# Sport_Analyzer_Chronojump_Teensy_4.net
KiCad netlist of a schematic drawn in EAGLE
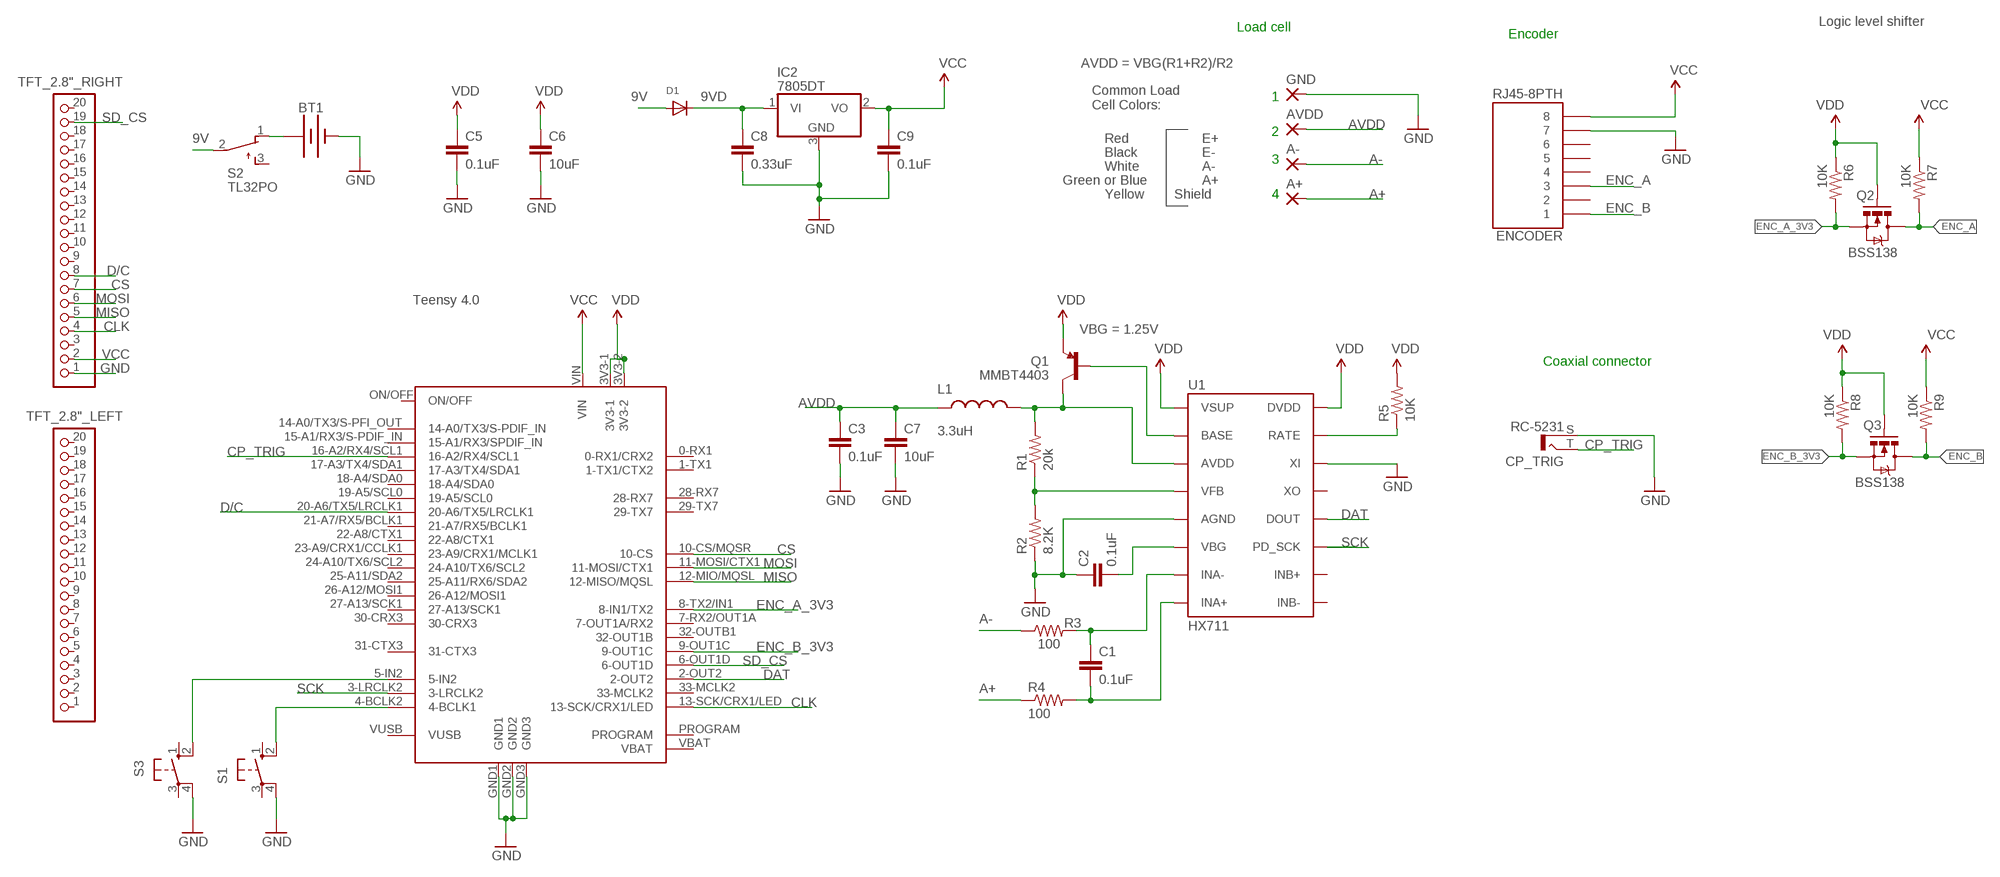
[diagram p0: schematic, sheet 1]

(export (version "E")
  (design (tool "Eeschema 10.0.6"))
  (components
    (comp (ref "A+")
      (value "3,81/1,4")
      (footprint "eagle-import:3,81_1,4")
      (libsource (lib "eagle-import") (part "3,81/1,4"))
    )
    (comp (ref "A-")
      (value "3,81/1,4")
      (footprint "eagle-import:3,81_1,4")
      (libsource (lib "eagle-import") (part "3,81/1,4"))
    )
    (comp (ref "AVDD")
      (value "3,81/1,4")
      (footprint "eagle-import:3,81_1,4")
      (libsource (lib "eagle-import") (part "3,81/1,4"))
    )
    (comp (ref "BT1")
      (value "BATTERY-9V")
      (footprint "eagle-import:BATTCON_9V")
      (libsource (lib "eagle-import") (part "BATTERY-9V"))
    )
    (comp (ref "C1")
      (value "0.1uF")
      (footprint "eagle-import:0603-CAP")
      (libsource (lib "eagle-import") (part "0.1UF-25V-5%(0603)"))
    )
    (comp (ref "C2")
      (value "0.1uF")
      (footprint "eagle-import:0603-CAP")
      (libsource (lib "eagle-import") (part "0.1UF-25V-5%(0603)"))
    )
    (comp (ref "C3")
      (value "0.1uF")
      (footprint "eagle-import:0603-CAP")
      (libsource (lib "eagle-import") (part "0.1UF-25V-5%(0603)"))
    )
    (comp (ref "C5")
      (value "0.1uF")
      (footprint "eagle-import:0603-CAP")
      (libsource (lib "eagle-import") (part "0.1UF-25V-5%(0603)"))
    )
    (comp (ref "C6")
      (value "10uF")
      (footprint "eagle-import:1210")
      (libsource (lib "eagle-import") (part "10UF50V20%(1210)"))
    )
    (comp (ref "C7")
      (value "10uF")
      (footprint "eagle-import:1210")
      (libsource (lib "eagle-import") (part "10UF50V20%(1210)"))
    )
    (comp (ref "C8")
      (value "0.33uF")
      (footprint "eagle-import:0603-CAP")
      (libsource (lib "eagle-import") (part "0.1UF-25V-5%(0603)"))
    )
    (comp (ref "C9")
      (value "0.1uF")
      (footprint "eagle-import:0603-CAP")
      (libsource (lib "eagle-import") (part "0.1UF-25V-5%(0603)"))
    )
    (comp (ref "CP_TRIG")
      (value "RC-5231")
      (footprint "eagle-import:RC-5231")
      (libsource (lib "eagle-import") (part "RC-5231"))
    )
    (comp (ref "D1")
      (value "DIODESOD-123")
      (footprint "eagle-import:SOD-123")
      (libsource (lib "eagle-import") (part "DIODESOD-123"))
    )
    (comp (ref "ENCODER")
      (value "RJ45-8PTH")
      (footprint "eagle-import:RJ45-8")
      (libsource (lib "eagle-import") (part "RJ45-8PTH"))
    )
    (comp (ref "GND")
      (value "3,81/1,4")
      (footprint "eagle-import:3,81_1,4")
      (libsource (lib "eagle-import") (part "3,81/1,4"))
    )
    (comp (ref "IC2")
      (value "7805DT")
      (footprint "eagle-import:TO252")
      (libsource (lib "eagle-import") (part "78DT05"))
    )
    (comp (ref "L1")
      (value "3.3uH")
      (footprint "eagle-import:0805")
      (libsource (lib "eagle-import") (part "INDUCTOR0805-IND"))
    )
    (comp (ref "Q1")
      (value "MMBT4403")
      (footprint "eagle-import:SOT23-3")
      (libsource (lib "eagle-import") (part "TRANSISTOR_PNPMMBT4403"))
    )
    (comp (ref "Q2")
      (value "BSS138")
      (footprint "eagle-import:SOT23-3")
      (libsource (lib "eagle-import") (part "MOSFET-NCHANNELSMD"))
    )
    (comp (ref "Q3")
      (value "BSS138")
      (footprint "eagle-import:SOT23-3")
      (libsource (lib "eagle-import") (part "MOSFET-NCHANNELSMD"))
    )
    (comp (ref "R1")
      (value "20k")
      (footprint "eagle-import:0603-RES")
      (libsource (lib "eagle-import") (part "20KOHM1/10W1%(0603)"))
    )
    (comp (ref "R2")
      (value "8.2K")
      (footprint "eagle-import:0603-RES")
      (libsource (lib "eagle-import") (part "8.2KOHM-1/10W-5%(0603)"))
    )
    (comp (ref "R3")
      (value "100")
      (footprint "eagle-import:0603-RES")
      (libsource (lib "eagle-import") (part "100OHM-1/10W-1%(0603)"))
    )
    (comp (ref "R4")
      (value "100")
      (footprint "eagle-import:0603-RES")
      (libsource (lib "eagle-import") (part "100OHM-1/10W-1%(0603)"))
    )
    (comp (ref "R5")
      (value "10K")
      (footprint "eagle-import:0603-RES")
      (libsource (lib "eagle-import") (part "10KOHM-1/10W-1%(0603)0603"))
    )
    (comp (ref "R6")
      (value "10K")
      (footprint "eagle-import:0603-RES")
      (libsource (lib "eagle-import") (part "RESISTOR0603-RES"))
    )
    (comp (ref "R7")
      (value "10K")
      (footprint "eagle-import:0603-RES")
      (libsource (lib "eagle-import") (part "RESISTOR0603-RES"))
    )
    (comp (ref "R8")
      (value "10K")
      (footprint "eagle-import:0603-RES")
      (libsource (lib "eagle-import") (part "RESISTOR0603-RES"))
    )
    (comp (ref "R9")
      (value "10K")
      (footprint "eagle-import:0603-RES")
      (libsource (lib "eagle-import") (part "RESISTOR0603-RES"))
    )
    (comp (ref "S1")
      (value "10-XX")
      (footprint "eagle-import:B3F-10XX")
      (fields (field (name "MPN") "B3F-1000"))
      (libsource (lib "eagle-import") (part "10-XX"))
    )
    (comp (ref "S2")
      (value "TL32PO")
      (footprint "eagle-import:TL3XPO")
      (libsource (lib "eagle-import") (part "TL32PO"))
    )
    (comp (ref "S3")
      (value "10-XX")
      (footprint "eagle-import:B3F-10XX")
      (fields (field (name "MPN") "B3F-1000"))
      (libsource (lib "eagle-import") (part "10-XX"))
    )
    (comp (ref "TFT_2.8\"_LEFT")
      (value "PINHD-1X20")
      (footprint "eagle-import:1X20")
      (libsource (lib "eagle-import") (part "PINHD-1X20"))
    )
    (comp (ref "TFT_2.8\"_RIGHT")
      (value "PINHD-1X20")
      (footprint "eagle-import:1X20")
      (libsource (lib "eagle-import") (part "PINHD-1X20"))
    )
    (comp (ref "U$2")
      (value "TEENSY40")
      (footprint "eagle-import:TEENSY40")
      (libsource (lib "eagle-import") (part "TEENSY40"))
    )
    (comp (ref "U1")
      (value "HX711")
      (footprint "eagle-import:SO16")
      (libsource (lib "eagle-import") (part "HX711HX711"))
    )
  )
  (nets
    (net (code "1") (name "/9V") (class "Default")
      (node (ref "D1") (pin "A") (pinfunction "A_A") (pintype "passive"))
      (node (ref "S2") (pin "2") (pinfunction "P_2") (pintype "passive"))
    )
    (net (code "2") (name "/9VD") (class "Default")
      (node (ref "C8") (pin "1") (pinfunction "1_1") (pintype "passive"))
      (node (ref "D1") (pin "C") (pinfunction "C_C") (pintype "passive"))
      (node (ref "IC2") (pin "1") (pinfunction "VI_1") (pintype "input"))
    )
    (net (code "3") (name "/A+") (class "Default")
      (node (ref "A+") (pin "1") (pinfunction "P_1") (pintype "passive"))
      (node (ref "R4") (pin "1") (pinfunction "1_1") (pintype "passive"))
    )
    (net (code "4") (name "/A-") (class "Default")
      (node (ref "A-") (pin "1") (pinfunction "P_1") (pintype "passive"))
      (node (ref "R3") (pin "1") (pinfunction "1_1") (pintype "passive"))
    )
    (net (code "5") (name "/AVDD") (class "Default")
      (node (ref "AVDD") (pin "1") (pinfunction "P_1") (pintype "passive"))
      (node (ref "C3") (pin "1") (pinfunction "1_1") (pintype "passive"))
      (node (ref "C7") (pin "1") (pinfunction "1_1") (pintype "passive"))
      (node (ref "L1") (pin "1") (pinfunction "1_1") (pintype "passive"))
    )
    (net (code "6") (name "/CLK") (class "Default")
      (node (ref "TFT_2.8\"_RIGHT") (pin "4") (pinfunction "4_4") (pintype "passive"))
      (node (ref "U$2") (pin "13-SCK/CRX1/LED") (pinfunction "13-SCK/CRX1/LED_13-SCK/CRX1/LED") (pintype "bidirectional"))
    )
    (net (code "7") (name "/CP_TRIG") (class "Default")
      (node (ref "CP_TRIG") (pin "T") (pinfunction "T_T") (pintype "passive"))
      (node (ref "U$2") (pin "16-A2/RX4/SCL1") (pinfunction "16-A2/RX4/SCL1_16-A2/RX4/SCL1") (pintype "bidirectional"))
    )
    (net (code "8") (name "/CS") (class "Default")
      (node (ref "TFT_2.8\"_RIGHT") (pin "7") (pinfunction "7_7") (pintype "passive"))
      (node (ref "U$2") (pin "10-CS/MQSR") (pinfunction "10-CS_10-CS/MQSR") (pintype "bidirectional"))
    )
    (net (code "9") (name "/DAT") (class "Default")
      (node (ref "U$2") (pin "2-OUT2") (pinfunction "2-OUT2_2-OUT2") (pintype "bidirectional"))
      (node (ref "U1") (pin "12") (pinfunction "DOUT_12") (pintype "bidirectional"))
    )
    (net (code "10") (name "/D{slash}C") (class "Default")
      (node (ref "TFT_2.8\"_RIGHT") (pin "8") (pinfunction "8_8") (pintype "passive"))
      (node (ref "U$2") (pin "20-A6/TX5/LRCLK1") (pinfunction "20-A6/TX5/LRCLK1_20-A6/TX5/LRCLK1") (pintype "bidirectional"))
    )
    (net (code "11") (name "/MISO") (class "Default")
      (node (ref "TFT_2.8\"_RIGHT") (pin "5") (pinfunction "5_5") (pintype "passive"))
      (node (ref "U$2") (pin "12-MIO/MQSL") (pinfunction "12-MISO/MQSL_12-MIO/MQSL") (pintype "bidirectional"))
    )
    (net (code "12") (name "/MOSI") (class "Default")
      (node (ref "TFT_2.8\"_RIGHT") (pin "6") (pinfunction "6_6") (pintype "passive"))
      (node (ref "U$2") (pin "11-MOSI/CTX1") (pinfunction "11-MOSI/CTX1_11-MOSI/CTX1") (pintype "bidirectional"))
    )
    (net (code "13") (name "/SCK") (class "Default")
      (node (ref "U$2") (pin "3-LRCLK2") (pinfunction "3-LRCLK2_3-LRCLK2") (pintype "bidirectional"))
      (node (ref "U1") (pin "11") (pinfunction "PD_SCK_11") (pintype "bidirectional"))
    )
    (net (code "14") (name "/SD_CS") (class "Default")
      (node (ref "TFT_2.8\"_RIGHT") (pin "19") (pinfunction "19_19") (pintype "passive"))
      (node (ref "U$2") (pin "6-OUT1D") (pinfunction "6-OUT1D_6-OUT1D") (pintype "bidirectional"))
    )
    (net (code "15") (name "ENC_A") (class "Default")
      (node (ref "ENCODER") (pin "3") (pinfunction "3_3") (pintype "bidirectional"))
      (node (ref "Q2") (pin "3") (pinfunction "D_3") (pintype "passive"))
      (node (ref "R7") (pin "2") (pinfunction "2_2") (pintype "passive"))
    )
    (net (code "16") (name "ENC_A_3V3") (class "Default")
      (node (ref "Q2") (pin "2") (pinfunction "S_2") (pintype "passive"))
      (node (ref "R6") (pin "2") (pinfunction "2_2") (pintype "passive"))
      (node (ref "U$2") (pin "8-TX2/IN1") (pinfunction "8-IN1/TX2_8-TX2/IN1") (pintype "bidirectional"))
    )
    (net (code "17") (name "ENC_B") (class "Default")
      (node (ref "ENCODER") (pin "1") (pinfunction "1_1") (pintype "bidirectional"))
      (node (ref "Q3") (pin "3") (pinfunction "D_3") (pintype "passive"))
      (node (ref "R9") (pin "2") (pinfunction "2_2") (pintype "passive"))
    )
    (net (code "18") (name "ENC_B_3V3") (class "Default")
      (node (ref "Q3") (pin "2") (pinfunction "S_2") (pintype "passive"))
      (node (ref "R8") (pin "2") (pinfunction "2_2") (pintype "passive"))
      (node (ref "U$2") (pin "9-OUT1C") (pinfunction "9-OUT1C_9-OUT1C") (pintype "bidirectional"))
    )
    (net (code "19") (name "GND") (class "Default")
      (node (ref "BT1") (pin "-") (pinfunction "-_-") (pintype "power_in"))
      (node (ref "C2") (pin "1") (pinfunction "1_1") (pintype "passive"))
      (node (ref "C3") (pin "2") (pinfunction "2_2") (pintype "passive"))
      (node (ref "C5") (pin "2") (pinfunction "2_2") (pintype "passive"))
      (node (ref "C6") (pin "2") (pinfunction "2_2") (pintype "passive"))
      (node (ref "C7") (pin "2") (pinfunction "2_2") (pintype "passive"))
      (node (ref "C8") (pin "2") (pinfunction "2_2") (pintype "passive"))
      (node (ref "C9") (pin "2") (pinfunction "2_2") (pintype "passive"))
      (node (ref "CP_TRIG") (pin "S") (pinfunction "S_S") (pintype "passive"))
      (node (ref "ENCODER") (pin "7") (pinfunction "7_7") (pintype "bidirectional"))
      (node (ref "GND") (pin "1") (pinfunction "P_1") (pintype "passive"))
      (node (ref "IC2") (pin "3") (pinfunction "GND_3") (pintype "passive"))
      (node (ref "R2") (pin "1") (pinfunction "1_1") (pintype "passive"))
      (node (ref "S1") (pin "4") (pinfunction "P1_4") (pintype "passive"))
      (node (ref "S3") (pin "4") (pinfunction "P1_4") (pintype "passive"))
      (node (ref "TFT_2.8\"_RIGHT") (pin "1") (pinfunction "1_1") (pintype "passive"))
      (node (ref "U$2") (pin "GND1") (pinfunction "GND1_GND1") (pintype "bidirectional"))
      (node (ref "U$2") (pin "GND2") (pinfunction "GND2_GND2") (pintype "bidirectional"))
      (node (ref "U$2") (pin "GND3") (pinfunction "GND3_GND3") (pintype "bidirectional"))
      (node (ref "U1") (pin "14") (pinfunction "XI_14") (pintype "bidirectional"))
      (node (ref "U1") (pin "5") (pinfunction "AGND_5") (pintype "bidirectional"))
    )
    (net (code "20") (name "Net-(Q1-B)") (class "Default")
      (node (ref "Q1") (pin "1") (pinfunction "B_1") (pintype "passive"))
      (node (ref "U1") (pin "2") (pinfunction "BASE_2") (pintype "bidirectional"))
    )
    (net (code "21") (name "Net-(Q1-C)") (class "Default")
      (node (ref "L1") (pin "2") (pinfunction "2_2") (pintype "passive"))
      (node (ref "Q1") (pin "3") (pinfunction "C_3") (pintype "passive"))
      (node (ref "R1") (pin "2") (pinfunction "2_2") (pintype "passive"))
      (node (ref "U1") (pin "3") (pinfunction "AVDD_3") (pintype "bidirectional"))
    )
    (net (code "22") (name "Net-(S1-S1)") (class "Default")
      (node (ref "S1") (pin "2") (pinfunction "S1_2") (pintype "passive"))
      (node (ref "U$2") (pin "4-BCLK2") (pinfunction "4-BCLK1_4-BCLK2") (pintype "bidirectional"))
    )
    (net (code "23") (name "Net-(S2-O)") (class "Default")
      (node (ref "BT1") (pin "+") (pinfunction "+_+") (pintype "power_in"))
      (node (ref "S2") (pin "1") (pinfunction "O_1") (pintype "passive"))
    )
    (net (code "24") (name "Net-(S3-S1)") (class "Default")
      (node (ref "S3") (pin "2") (pinfunction "S1_2") (pintype "passive"))
      (node (ref "U$2") (pin "5-IN2") (pinfunction "5-IN2_5-IN2") (pintype "bidirectional"))
    )
    (net (code "25") (name "Net-(U1-INA+)") (class "Default")
      (node (ref "C1") (pin "2") (pinfunction "2_2") (pintype "passive"))
      (node (ref "R4") (pin "2") (pinfunction "2_2") (pintype "passive"))
      (node (ref "U1") (pin "8") (pinfunction "INA+_8") (pintype "bidirectional"))
    )
    (net (code "26") (name "Net-(U1-INA-)") (class "Default")
      (node (ref "C1") (pin "1") (pinfunction "1_1") (pintype "passive"))
      (node (ref "R3") (pin "2") (pinfunction "2_2") (pintype "passive"))
      (node (ref "U1") (pin "7") (pinfunction "INA-_7") (pintype "bidirectional"))
    )
    (net (code "27") (name "Net-(U1-RATE)") (class "Default")
      (node (ref "R5") (pin "1") (pinfunction "1_1") (pintype "passive"))
      (node (ref "U1") (pin "15") (pinfunction "RATE_15") (pintype "bidirectional"))
    )
    (net (code "28") (name "Net-(U1-VBG)") (class "Default")
      (node (ref "C2") (pin "2") (pinfunction "2_2") (pintype "passive"))
      (node (ref "U1") (pin "6") (pinfunction "VBG_6") (pintype "bidirectional"))
    )
    (net (code "29") (name "Net-(U1-VFB)") (class "Default")
      (node (ref "R1") (pin "1") (pinfunction "1_1") (pintype "passive"))
      (node (ref "R2") (pin "2") (pinfunction "2_2") (pintype "passive"))
      (node (ref "U1") (pin "4") (pinfunction "VFB_4") (pintype "bidirectional"))
    )
    (net (code "30") (name "VCC") (class "Default")
      (node (ref "C9") (pin "1") (pinfunction "1_1") (pintype "passive"))
      (node (ref "ENCODER") (pin "8") (pinfunction "8_8") (pintype "bidirectional"))
      (node (ref "IC2") (pin "2") (pinfunction "VO_2") (pintype "passive"))
      (node (ref "R7") (pin "1") (pinfunction "1_1") (pintype "passive"))
      (node (ref "R9") (pin "1") (pinfunction "1_1") (pintype "passive"))
      (node (ref "TFT_2.8\"_RIGHT") (pin "2") (pinfunction "2_2") (pintype "passive"))
      (node (ref "U$2") (pin "VIN") (pinfunction "VIN_VIN") (pintype "bidirectional"))
    )
    (net (code "31") (name "VDD") (class "Default")
      (node (ref "C5") (pin "1") (pinfunction "1_1") (pintype "passive"))
      (node (ref "C6") (pin "1") (pinfunction "1_1") (pintype "passive"))
      (node (ref "Q1") (pin "2") (pinfunction "E_2") (pintype "passive"))
      (node (ref "Q2") (pin "1") (pinfunction "G_1") (pintype "passive"))
      (node (ref "Q3") (pin "1") (pinfunction "G_1") (pintype "passive"))
      (node (ref "R5") (pin "2") (pinfunction "2_2") (pintype "passive"))
      (node (ref "R6") (pin "1") (pinfunction "1_1") (pintype "passive"))
      (node (ref "R8") (pin "1") (pinfunction "1_1") (pintype "passive"))
      (node (ref "U$2") (pin "3V3-1") (pinfunction "3V3-1_3V3-1") (pintype "bidirectional"))
      (node (ref "U$2") (pin "3V3-2") (pinfunction "3V3-2_3V3-2") (pintype "bidirectional"))
      (node (ref "U1") (pin "1") (pinfunction "VSUP_1") (pintype "bidirectional"))
      (node (ref "U1") (pin "16") (pinfunction "DVDD_16") (pintype "bidirectional"))
    )
    (net (code "32") (name "unconnected-(ENCODER-Pad2)") (class "Default")
      (node (ref "ENCODER") (pin "2") (pinfunction "2_2") (pintype "bidirectional"))
    )
    (net (code "33") (name "unconnected-(ENCODER-Pad4)") (class "Default")
      (node (ref "ENCODER") (pin "4") (pinfunction "4_4") (pintype "bidirectional"))
    )
    (net (code "34") (name "unconnected-(ENCODER-Pad5)") (class "Default")
      (node (ref "ENCODER") (pin "5") (pinfunction "5_5") (pintype "bidirectional"))
    )
    (net (code "35") (name "unconnected-(ENCODER-Pad6)") (class "Default")
      (node (ref "ENCODER") (pin "6") (pinfunction "6_6") (pintype "bidirectional"))
    )
    (net (code "36") (name "unconnected-(S1-P-Pad3)") (class "Default")
      (node (ref "S1") (pin "3") (pinfunction "P_3") (pintype "passive"))
    )
    (net (code "37") (name "unconnected-(S1-S-Pad1)") (class "Default")
      (node (ref "S1") (pin "1") (pinfunction "S_1") (pintype "passive"))
    )
    (net (code "38") (name "unconnected-(S2-S-Pad3)") (class "Default")
      (node (ref "S2") (pin "3") (pinfunction "S_3") (pintype "passive"))
    )
    (net (code "39") (name "unconnected-(S3-P-Pad3)") (class "Default")
      (node (ref "S3") (pin "3") (pinfunction "P_3") (pintype "passive"))
    )
    (net (code "40") (name "unconnected-(S3-S-Pad1)") (class "Default")
      (node (ref "S3") (pin "1") (pinfunction "S_1") (pintype "passive"))
    )
    (net (code "41") (name "unconnected-(TFT_2.8\"_LEFT-Pad1)") (class "Default")
      (node (ref "TFT_2.8\"_LEFT") (pin "1") (pinfunction "1_1") (pintype "passive"))
    )
    (net (code "42") (name "unconnected-(TFT_2.8\"_LEFT-Pad2)") (class "Default")
      (node (ref "TFT_2.8\"_LEFT") (pin "2") (pinfunction "2_2") (pintype "passive"))
    )
    (net (code "43") (name "unconnected-(TFT_2.8\"_LEFT-Pad3)") (class "Default")
      (node (ref "TFT_2.8\"_LEFT") (pin "3") (pinfunction "3_3") (pintype "passive"))
    )
    (net (code "44") (name "unconnected-(TFT_2.8\"_LEFT-Pad4)") (class "Default")
      (node (ref "TFT_2.8\"_LEFT") (pin "4") (pinfunction "4_4") (pintype "passive"))
    )
    (net (code "45") (name "unconnected-(TFT_2.8\"_LEFT-Pad5)") (class "Default")
      (node (ref "TFT_2.8\"_LEFT") (pin "5") (pinfunction "5_5") (pintype "passive"))
    )
    (net (code "46") (name "unconnected-(TFT_2.8\"_LEFT-Pad6)") (class "Default")
      (node (ref "TFT_2.8\"_LEFT") (pin "6") (pinfunction "6_6") (pintype "passive"))
    )
    (net (code "47") (name "unconnected-(TFT_2.8\"_LEFT-Pad7)") (class "Default")
      (node (ref "TFT_2.8\"_LEFT") (pin "7") (pinfunction "7_7") (pintype "passive"))
    )
    (net (code "48") (name "unconnected-(TFT_2.8\"_LEFT-Pad8)") (class "Default")
      (node (ref "TFT_2.8\"_LEFT") (pin "8") (pinfunction "8_8") (pintype "passive"))
    )
    (net (code "49") (name "unconnected-(TFT_2.8\"_LEFT-Pad9)") (class "Default")
      (node (ref "TFT_2.8\"_LEFT") (pin "9") (pinfunction "9_9") (pintype "passive"))
    )
    (net (code "50") (name "unconnected-(TFT_2.8\"_LEFT-Pad10)") (class "Default")
      (node (ref "TFT_2.8\"_LEFT") (pin "10") (pinfunction "10_10") (pintype "passive"))
    )
    (net (code "51") (name "unconnected-(TFT_2.8\"_LEFT-Pad11)") (class "Default")
      (node (ref "TFT_2.8\"_LEFT") (pin "11") (pinfunction "11_11") (pintype "passive"))
    )
    (net (code "52") (name "unconnected-(TFT_2.8\"_LEFT-Pad12)") (class "Default")
      (node (ref "TFT_2.8\"_LEFT") (pin "12") (pinfunction "12_12") (pintype "passive"))
    )
    (net (code "53") (name "unconnected-(TFT_2.8\"_LEFT-Pad13)") (class "Default")
      (node (ref "TFT_2.8\"_LEFT") (pin "13") (pinfunction "13_13") (pintype "passive"))
    )
    (net (code "54") (name "unconnected-(TFT_2.8\"_LEFT-Pad14)") (class "Default")
      (node (ref "TFT_2.8\"_LEFT") (pin "14") (pinfunction "14_14") (pintype "passive"))
    )
    (net (code "55") (name "unconnected-(TFT_2.8\"_LEFT-Pad15)") (class "Default")
      (node (ref "TFT_2.8\"_LEFT") (pin "15") (pinfunction "15_15") (pintype "passive"))
    )
    (net (code "56") (name "unconnected-(TFT_2.8\"_LEFT-Pad16)") (class "Default")
      (node (ref "TFT_2.8\"_LEFT") (pin "16") (pinfunction "16_16") (pintype "passive"))
    )
    (net (code "57") (name "unconnected-(TFT_2.8\"_LEFT-Pad17)") (class "Default")
      (node (ref "TFT_2.8\"_LEFT") (pin "17") (pinfunction "17_17") (pintype "passive"))
    )
    (net (code "58") (name "unconnected-(TFT_2.8\"_LEFT-Pad18)") (class "Default")
      (node (ref "TFT_2.8\"_LEFT") (pin "18") (pinfunction "18_18") (pintype "passive"))
    )
    (net (code "59") (name "unconnected-(TFT_2.8\"_LEFT-Pad19)") (class "Default")
      (node (ref "TFT_2.8\"_LEFT") (pin "19") (pinfunction "19_19") (pintype "passive"))
    )
    (net (code "60") (name "unconnected-(TFT_2.8\"_LEFT-Pad20)") (class "Default")
      (node (ref "TFT_2.8\"_LEFT") (pin "20") (pinfunction "20_20") (pintype "passive"))
    )
    (net (code "61") (name "unconnected-(TFT_2.8\"_RIGHT-Pad3)") (class "Default")
      (node (ref "TFT_2.8\"_RIGHT") (pin "3") (pinfunction "3_3") (pintype "passive"))
    )
    (net (code "62") (name "unconnected-(TFT_2.8\"_RIGHT-Pad9)") (class "Default")
      (node (ref "TFT_2.8\"_RIGHT") (pin "9") (pinfunction "9_9") (pintype "passive"))
    )
    (net (code "63") (name "unconnected-(TFT_2.8\"_RIGHT-Pad10)") (class "Default")
      (node (ref "TFT_2.8\"_RIGHT") (pin "10") (pinfunction "10_10") (pintype "passive"))
    )
    (net (code "64") (name "unconnected-(TFT_2.8\"_RIGHT-Pad11)") (class "Default")
      (node (ref "TFT_2.8\"_RIGHT") (pin "11") (pinfunction "11_11") (pintype "passive"))
    )
    (net (code "65") (name "unconnected-(TFT_2.8\"_RIGHT-Pad12)") (class "Default")
      (node (ref "TFT_2.8\"_RIGHT") (pin "12") (pinfunction "12_12") (pintype "passive"))
    )
    (net (code "66") (name "unconnected-(TFT_2.8\"_RIGHT-Pad13)") (class "Default")
      (node (ref "TFT_2.8\"_RIGHT") (pin "13") (pinfunction "13_13") (pintype "passive"))
    )
    (net (code "67") (name "unconnected-(TFT_2.8\"_RIGHT-Pad14)") (class "Default")
      (node (ref "TFT_2.8\"_RIGHT") (pin "14") (pinfunction "14_14") (pintype "passive"))
    )
    (net (code "68") (name "unconnected-(TFT_2.8\"_RIGHT-Pad15)") (class "Default")
      (node (ref "TFT_2.8\"_RIGHT") (pin "15") (pinfunction "15_15") (pintype "passive"))
    )
    (net (code "69") (name "unconnected-(TFT_2.8\"_RIGHT-Pad16)") (class "Default")
      (node (ref "TFT_2.8\"_RIGHT") (pin "16") (pinfunction "16_16") (pintype "passive"))
    )
    (net (code "70") (name "unconnected-(TFT_2.8\"_RIGHT-Pad17)") (class "Default")
      (node (ref "TFT_2.8\"_RIGHT") (pin "17") (pinfunction "17_17") (pintype "passive"))
    )
    (net (code "71") (name "unconnected-(TFT_2.8\"_RIGHT-Pad18)") (class "Default")
      (node (ref "TFT_2.8\"_RIGHT") (pin "18") (pinfunction "18_18") (pintype "passive"))
    )
    (net (code "72") (name "unconnected-(TFT_2.8\"_RIGHT-Pad20)") (class "Default")
      (node (ref "TFT_2.8\"_RIGHT") (pin "20") (pinfunction "20_20") (pintype "passive"))
    )
    (net (code "73") (name "unconnected-(U$2-0-RX1{slash}CRX2-Pad0-RX1)") (class "Default")
      (node (ref "U$2") (pin "0-RX1") (pinfunction "0-RX1/CRX2_0-RX1") (pintype "bidirectional"))
    )
    (net (code "74") (name "unconnected-(U$2-1-TX1{slash}CTX2-Pad1-TX1)") (class "Default")
      (node (ref "U$2") (pin "1-TX1") (pinfunction "1-TX1/CTX2_1-TX1") (pintype "bidirectional"))
    )
    (net (code "75") (name "unconnected-(U$2-7-OUT1A{slash}RX2-Pad7-RX2{slash}OUT1A)") (class "Default")
      (node (ref "U$2") (pin "7-RX2/OUT1A") (pinfunction "7-OUT1A/RX2_7-RX2/OUT1A") (pintype "bidirectional"))
    )
    (net (code "76") (name "unconnected-(U$2-14-A0{slash}TX3{slash}S-PDIF_IN-Pad14-A0{slash}TX3{slash}S-PFI_OUT)") (class "Default")
      (node (ref "U$2") (pin "14-A0/TX3/S-PFI_OUT") (pinfunction "14-A0/TX3/S-PDIF_IN_14-A0/TX3/S-PFI_OUT") (pintype "bidirectional"))
    )
    (net (code "77") (name "unconnected-(U$2-15-A1{slash}RX3{slash}SPDIF_IN-Pad15-A1{slash}RX3{slash}S-PDIF_IN)") (class "Default")
      (node (ref "U$2") (pin "15-A1/RX3/S-PDIF_IN") (pinfunction "15-A1/RX3/SPDIF_IN_15-A1/RX3/S-PDIF_IN") (pintype "bidirectional"))
    )
    (net (code "78") (name "unconnected-(U$2-23-A9{slash}CRX1{slash}MCLK1-Pad23-A9{slash}CRX1{slash}CCLK1)") (class "Default")
      (node (ref "U$2") (pin "23-A9/CRX1/CCLK1") (pinfunction "23-A9/CRX1/MCLK1_23-A9/CRX1/CCLK1") (pintype "bidirectional"))
    )
    (net (code "79") (name "unconnected-(U$2-25-A11{slash}RX6{slash}SDA2-Pad25-A11{slash}SDA2)") (class "Default")
      (node (ref "U$2") (pin "25-A11/SDA2") (pinfunction "25-A11/RX6/SDA2_25-A11/SDA2") (pintype "bidirectional"))
    )
    (net (code "80") (name "unconnected-(U$2-32-OUT1B-Pad32-OUTB1)") (class "Default")
      (node (ref "U$2") (pin "32-OUTB1") (pinfunction "32-OUT1B_32-OUTB1") (pintype "bidirectional"))
    )
    (net (code "81") (name "unconnected-(U$2-Pad17-A3{slash}TX4{slash}SDA1)") (class "Default")
      (node (ref "U$2") (pin "17-A3/TX4/SDA1") (pinfunction "17-A3/TX4/SDA1_17-A3/TX4/SDA1") (pintype "bidirectional"))
    )
    (net (code "82") (name "unconnected-(U$2-Pad18-A4{slash}SDA0)") (class "Default")
      (node (ref "U$2") (pin "18-A4/SDA0") (pinfunction "18-A4/SDA0_18-A4/SDA0") (pintype "bidirectional"))
    )
    (net (code "83") (name "unconnected-(U$2-Pad19-A5{slash}SCL0)") (class "Default")
      (node (ref "U$2") (pin "19-A5/SCL0") (pinfunction "19-A5/SCL0_19-A5/SCL0") (pintype "bidirectional"))
    )
    (net (code "84") (name "unconnected-(U$2-Pad21-A7{slash}RX5{slash}BCLK1)") (class "Default")
      (node (ref "U$2") (pin "21-A7/RX5/BCLK1") (pinfunction "21-A7/RX5/BCLK1_21-A7/RX5/BCLK1") (pintype "bidirectional"))
    )
    (net (code "85") (name "unconnected-(U$2-Pad22-A8{slash}CTX1)") (class "Default")
      (node (ref "U$2") (pin "22-A8/CTX1") (pinfunction "22-A8/CTX1_22-A8/CTX1") (pintype "bidirectional"))
    )
    (net (code "86") (name "unconnected-(U$2-Pad24-A10{slash}TX6{slash}SCL2)") (class "Default")
      (node (ref "U$2") (pin "24-A10/TX6/SCL2") (pinfunction "24-A10/TX6/SCL2_24-A10/TX6/SCL2") (pintype "bidirectional"))
    )
    (net (code "87") (name "unconnected-(U$2-Pad26-A12{slash}MOSI1)") (class "Default")
      (node (ref "U$2") (pin "26-A12/MOSI1") (pinfunction "26-A12/MOSI1_26-A12/MOSI1") (pintype "bidirectional"))
    )
    (net (code "88") (name "unconnected-(U$2-Pad27-A13{slash}SCK1)") (class "Default")
      (node (ref "U$2") (pin "27-A13/SCK1") (pinfunction "27-A13/SCK1_27-A13/SCK1") (pintype "bidirectional"))
    )
    (net (code "89") (name "unconnected-(U$2-Pad28-RX7)") (class "Default")
      (node (ref "U$2") (pin "28-RX7") (pinfunction "28-RX7_28-RX7") (pintype "bidirectional"))
    )
    (net (code "90") (name "unconnected-(U$2-Pad29-TX7)") (class "Default")
      (node (ref "U$2") (pin "29-TX7") (pinfunction "29-TX7_29-TX7") (pintype "bidirectional"))
    )
    (net (code "91") (name "unconnected-(U$2-Pad30-CRX3)") (class "Default")
      (node (ref "U$2") (pin "30-CRX3") (pinfunction "30-CRX3_30-CRX3") (pintype "bidirectional"))
    )
    (net (code "92") (name "unconnected-(U$2-Pad31-CTX3)") (class "Default")
      (node (ref "U$2") (pin "31-CTX3") (pinfunction "31-CTX3_31-CTX3") (pintype "bidirectional"))
    )
    (net (code "93") (name "unconnected-(U$2-Pad33-MCLK2)") (class "Default")
      (node (ref "U$2") (pin "33-MCLK2") (pinfunction "33-MCLK2_33-MCLK2") (pintype "bidirectional"))
    )
    (net (code "94") (name "unconnected-(U$2-PadON{slash}OFF)") (class "Default")
      (node (ref "U$2") (pin "ON/OFF") (pinfunction "ON/OFF_ON/OFF") (pintype "bidirectional"))
    )
    (net (code "95") (name "unconnected-(U$2-PadPROGRAM)") (class "Default")
      (node (ref "U$2") (pin "PROGRAM") (pinfunction "PROGRAM_PROGRAM") (pintype "bidirectional"))
    )
    (net (code "96") (name "unconnected-(U$2-PadVBAT)") (class "Default")
      (node (ref "U$2") (pin "VBAT") (pinfunction "VBAT_VBAT") (pintype "bidirectional"))
    )
    (net (code "97") (name "unconnected-(U$2-PadVUSB)") (class "Default")
      (node (ref "U$2") (pin "VUSB") (pinfunction "VUSB_VUSB") (pintype "bidirectional"))
    )
    (net (code "98") (name "unconnected-(U1-INB+-Pad10)") (class "Default")
      (node (ref "U1") (pin "10") (pinfunction "INB+_10") (pintype "bidirectional"))
    )
    (net (code "99") (name "unconnected-(U1-INB--Pad9)") (class "Default")
      (node (ref "U1") (pin "9") (pinfunction "INB-_9") (pintype "bidirectional"))
    )
    (net (code "100") (name "unconnected-(U1-XO-Pad13)") (class "Default")
      (node (ref "U1") (pin "13") (pinfunction "XO_13") (pintype "bidirectional"))
    )
  )
)
